# atxmega16d4simple.net
KiCad netlist of a schematic drawn in EAGLE
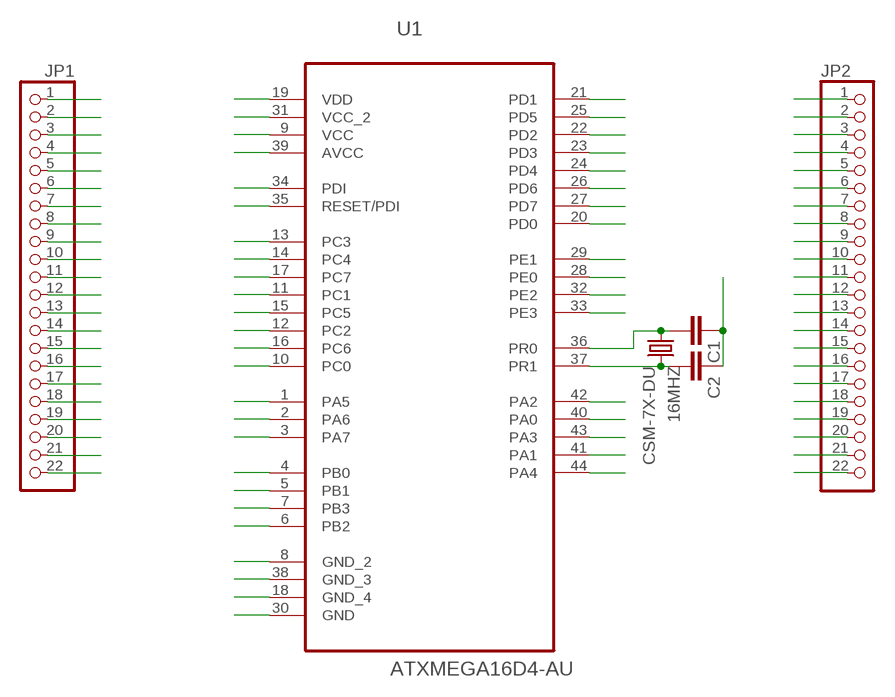
[diagram p0: schematic, sheet 1]

(export (version "E")
  (design (tool "Eeschema 10.0.6"))
  (components
    (comp (ref "16MHZ")
      (value "CSM-7X-DU")
      (footprint "eagle-import:CSM-7X-DU")
      (libsource (lib "eagle-import") (part "CSM-7X-DU"))
    )
    (comp (ref "C1")
      (value "C-EUC0805K")
      (footprint "eagle-import:C0805K")
      (libsource (lib "eagle-import") (part "C-EUC0805K"))
    )
    (comp (ref "C2")
      (value "C-EUC0805K")
      (footprint "eagle-import:C0805K")
      (libsource (lib "eagle-import") (part "C-EUC0805K"))
    )
    (comp (ref "JP1")
      (value "PINHD-1X22")
      (footprint "eagle-import:1X22")
      (libsource (lib "eagle-import") (part "PINHD-1X22"))
    )
    (comp (ref "JP2")
      (value "PINHD-1X22")
      (footprint "eagle-import:1X22")
      (libsource (lib "eagle-import") (part "PINHD-1X22"))
    )
    (comp (ref "U1")
      (value "ATXMEGA16D4-AU")
      (footprint "eagle-import:QFP80P1200X1200X120-44N")
      (libsource (lib "eagle-import") (part "ATXMEGA16D4-AU"))
    )
  )
  (nets
    (net (code "1") (name "/3.3V") (class "Default")
      (node (ref "JP1") (pin "19") (pinfunction "19_19") (pintype "passive"))
      (node (ref "JP1") (pin "9") (pinfunction "9_9") (pintype "passive"))
      (node (ref "JP2") (pin "9") (pinfunction "9_9") (pintype "passive"))
      (node (ref "U1") (pin "19") (pinfunction "VDD_19") (pintype "power_in"))
      (node (ref "U1") (pin "31") (pinfunction "VCC_2_31") (pintype "power_in"))
      (node (ref "U1") (pin "9") (pinfunction "VCC_9") (pintype "power_in"))
    )
    (net (code "2") (name "/AVCC") (class "Default")
      (node (ref "JP2") (pin "17") (pinfunction "17_17") (pintype "passive"))
      (node (ref "U1") (pin "39") (pinfunction "AVCC_39") (pintype "power_in"))
    )
    (net (code "3") (name "/GND") (class "Default")
      (node (ref "C1") (pin "1") (pinfunction "1_1") (pintype "passive"))
      (node (ref "C2") (pin "1") (pinfunction "1_1") (pintype "passive"))
      (node (ref "JP1") (pin "18") (pinfunction "18_18") (pintype "passive"))
      (node (ref "JP1") (pin "8") (pinfunction "8_8") (pintype "passive"))
      (node (ref "JP2") (pin "16") (pinfunction "16_16") (pintype "passive"))
      (node (ref "JP2") (pin "8") (pinfunction "8_8") (pintype "passive"))
      (node (ref "U1") (pin "18") (pinfunction "GND_4_18") (pintype "passive"))
      (node (ref "U1") (pin "30") (pinfunction "GND_30") (pintype "passive"))
      (node (ref "U1") (pin "38") (pinfunction "GND_3_38") (pintype "passive"))
      (node (ref "U1") (pin "8") (pinfunction "GND_2_8") (pintype "passive"))
    )
    (net (code "4") (name "/PA0") (class "Default")
      (node (ref "JP2") (pin "18") (pinfunction "18_18") (pintype "passive"))
      (node (ref "U1") (pin "40") (pinfunction "PA0_40") (pintype "bidirectional"))
    )
    (net (code "5") (name "/PA1") (class "Default")
      (node (ref "JP2") (pin "19") (pinfunction "19_19") (pintype "passive"))
      (node (ref "U1") (pin "41") (pinfunction "PA1_41") (pintype "bidirectional"))
    )
    (net (code "6") (name "/PA2") (class "Default")
      (node (ref "JP2") (pin "20") (pinfunction "20_20") (pintype "passive"))
      (node (ref "U1") (pin "42") (pinfunction "PA2_42") (pintype "bidirectional"))
    )
    (net (code "7") (name "/PA3") (class "Default")
      (node (ref "JP2") (pin "21") (pinfunction "21_21") (pintype "passive"))
      (node (ref "U1") (pin "43") (pinfunction "PA3_43") (pintype "bidirectional"))
    )
    (net (code "8") (name "/PA4") (class "Default")
      (node (ref "JP2") (pin "22") (pinfunction "22_22") (pintype "passive"))
      (node (ref "U1") (pin "44") (pinfunction "PA4_44") (pintype "bidirectional"))
    )
    (net (code "9") (name "/PA5") (class "Default")
      (node (ref "JP1") (pin "1") (pinfunction "1_1") (pintype "passive"))
      (node (ref "U1") (pin "1") (pinfunction "PA5_1") (pintype "bidirectional"))
    )
    (net (code "10") (name "/PA6") (class "Default")
      (node (ref "JP1") (pin "2") (pinfunction "2_2") (pintype "passive"))
      (node (ref "U1") (pin "2") (pinfunction "PA6_2") (pintype "bidirectional"))
    )
    (net (code "11") (name "/PA7") (class "Default")
      (node (ref "JP1") (pin "3") (pinfunction "3_3") (pintype "passive"))
      (node (ref "U1") (pin "3") (pinfunction "PA7_3") (pintype "bidirectional"))
    )
    (net (code "12") (name "/PB0") (class "Default")
      (node (ref "JP1") (pin "4") (pinfunction "4_4") (pintype "passive"))
      (node (ref "U1") (pin "4") (pinfunction "PB0_4") (pintype "bidirectional"))
    )
    (net (code "13") (name "/PB1") (class "Default")
      (node (ref "JP1") (pin "5") (pinfunction "5_5") (pintype "passive"))
      (node (ref "U1") (pin "5") (pinfunction "PB1_5") (pintype "bidirectional"))
    )
    (net (code "14") (name "/PB2") (class "Default")
      (node (ref "JP1") (pin "6") (pinfunction "6_6") (pintype "passive"))
      (node (ref "U1") (pin "6") (pinfunction "PB2_6") (pintype "bidirectional"))
    )
    (net (code "15") (name "/PB3") (class "Default")
      (node (ref "JP1") (pin "7") (pinfunction "7_7") (pintype "passive"))
      (node (ref "U1") (pin "7") (pinfunction "PB3_7") (pintype "bidirectional"))
    )
    (net (code "16") (name "/PC0") (class "Default")
      (node (ref "JP1") (pin "10") (pinfunction "10_10") (pintype "passive"))
      (node (ref "U1") (pin "10") (pinfunction "PC0_10") (pintype "bidirectional"))
    )
    (net (code "17") (name "/PC1") (class "Default")
      (node (ref "JP1") (pin "11") (pinfunction "11_11") (pintype "passive"))
      (node (ref "U1") (pin "11") (pinfunction "PC1_11") (pintype "bidirectional"))
    )
    (net (code "18") (name "/PC2") (class "Default")
      (node (ref "JP1") (pin "12") (pinfunction "12_12") (pintype "passive"))
      (node (ref "U1") (pin "12") (pinfunction "PC2_12") (pintype "bidirectional"))
    )
    (net (code "19") (name "/PC3") (class "Default")
      (node (ref "JP1") (pin "13") (pinfunction "13_13") (pintype "passive"))
      (node (ref "U1") (pin "13") (pinfunction "PC3_13") (pintype "bidirectional"))
    )
    (net (code "20") (name "/PC4") (class "Default")
      (node (ref "JP1") (pin "14") (pinfunction "14_14") (pintype "passive"))
      (node (ref "U1") (pin "14") (pinfunction "PC4_14") (pintype "bidirectional"))
    )
    (net (code "21") (name "/PC5") (class "Default")
      (node (ref "JP1") (pin "15") (pinfunction "15_15") (pintype "passive"))
      (node (ref "U1") (pin "15") (pinfunction "PC5_15") (pintype "bidirectional"))
    )
    (net (code "22") (name "/PC6") (class "Default")
      (node (ref "JP1") (pin "16") (pinfunction "16_16") (pintype "passive"))
      (node (ref "U1") (pin "16") (pinfunction "PC6_16") (pintype "bidirectional"))
    )
    (net (code "23") (name "/PC7") (class "Default")
      (node (ref "JP1") (pin "17") (pinfunction "17_17") (pintype "passive"))
      (node (ref "U1") (pin "17") (pinfunction "PC7_17") (pintype "bidirectional"))
    )
    (net (code "24") (name "/PD0") (class "Default")
      (node (ref "JP1") (pin "20") (pinfunction "20_20") (pintype "passive"))
      (node (ref "U1") (pin "20") (pinfunction "PD0_20") (pintype "bidirectional"))
    )
    (net (code "25") (name "/PD1") (class "Default")
      (node (ref "JP1") (pin "21") (pinfunction "21_21") (pintype "passive"))
      (node (ref "U1") (pin "21") (pinfunction "PD1_21") (pintype "bidirectional"))
    )
    (net (code "26") (name "/PD2") (class "Default")
      (node (ref "JP1") (pin "22") (pinfunction "22_22") (pintype "passive"))
      (node (ref "U1") (pin "22") (pinfunction "PD2_22") (pintype "bidirectional"))
    )
    (net (code "27") (name "/PD3") (class "Default")
      (node (ref "JP2") (pin "1") (pinfunction "1_1") (pintype "passive"))
      (node (ref "U1") (pin "23") (pinfunction "PD3_23") (pintype "bidirectional"))
    )
    (net (code "28") (name "/PD4") (class "Default")
      (node (ref "JP2") (pin "2") (pinfunction "2_2") (pintype "passive"))
      (node (ref "U1") (pin "24") (pinfunction "PD4_24") (pintype "bidirectional"))
    )
    (net (code "29") (name "/PD5") (class "Default")
      (node (ref "JP2") (pin "3") (pinfunction "3_3") (pintype "passive"))
      (node (ref "U1") (pin "25") (pinfunction "PD5_25") (pintype "bidirectional"))
    )
    (net (code "30") (name "/PD6") (class "Default")
      (node (ref "JP2") (pin "4") (pinfunction "4_4") (pintype "passive"))
      (node (ref "U1") (pin "26") (pinfunction "PD6_26") (pintype "bidirectional"))
    )
    (net (code "31") (name "/PD7") (class "Default")
      (node (ref "JP2") (pin "5") (pinfunction "5_5") (pintype "passive"))
      (node (ref "U1") (pin "27") (pinfunction "PD7_27") (pintype "bidirectional"))
    )
    (net (code "32") (name "/PDI") (class "Default")
      (node (ref "JP2") (pin "12") (pinfunction "12_12") (pintype "passive"))
      (node (ref "U1") (pin "34") (pinfunction "PDI_34") (pintype "passive"))
    )
    (net (code "33") (name "/PE0") (class "Default")
      (node (ref "JP2") (pin "6") (pinfunction "6_6") (pintype "passive"))
      (node (ref "U1") (pin "28") (pinfunction "PE0_28") (pintype "bidirectional"))
    )
    (net (code "34") (name "/PE1") (class "Default")
      (node (ref "JP2") (pin "7") (pinfunction "7_7") (pintype "passive"))
      (node (ref "U1") (pin "29") (pinfunction "PE1_29") (pintype "bidirectional"))
    )
    (net (code "35") (name "/PE2") (class "Default")
      (node (ref "JP2") (pin "10") (pinfunction "10_10") (pintype "passive"))
      (node (ref "U1") (pin "32") (pinfunction "PE2_32") (pintype "bidirectional"))
    )
    (net (code "36") (name "/PE3") (class "Default")
      (node (ref "JP2") (pin "11") (pinfunction "11_11") (pintype "passive"))
      (node (ref "U1") (pin "33") (pinfunction "PE3_33") (pintype "bidirectional"))
    )
    (net (code "37") (name "/PR0") (class "Default")
      (node (ref "16MHZ") (pin "1") (pinfunction "1_1") (pintype "passive"))
      (node (ref "C1") (pin "2") (pinfunction "2_2") (pintype "passive"))
      (node (ref "JP2") (pin "14") (pinfunction "14_14") (pintype "passive"))
      (node (ref "U1") (pin "36") (pinfunction "PR0_36") (pintype "bidirectional"))
    )
    (net (code "38") (name "/PR1") (class "Default")
      (node (ref "16MHZ") (pin "2") (pinfunction "2_2") (pintype "passive"))
      (node (ref "C2") (pin "2") (pinfunction "2_2") (pintype "passive"))
      (node (ref "JP2") (pin "15") (pinfunction "15_15") (pintype "passive"))
      (node (ref "U1") (pin "37") (pinfunction "PR1_37") (pintype "bidirectional"))
    )
    (net (code "39") (name "/RESET") (class "Default")
      (node (ref "JP2") (pin "13") (pinfunction "13_13") (pintype "passive"))
      (node (ref "U1") (pin "35") (pinfunction "RESET/PDI_35") (pintype "input"))
    )
  )
)
